# diffamp.net
KiCad netlist of a schematic drawn in Altium Designer
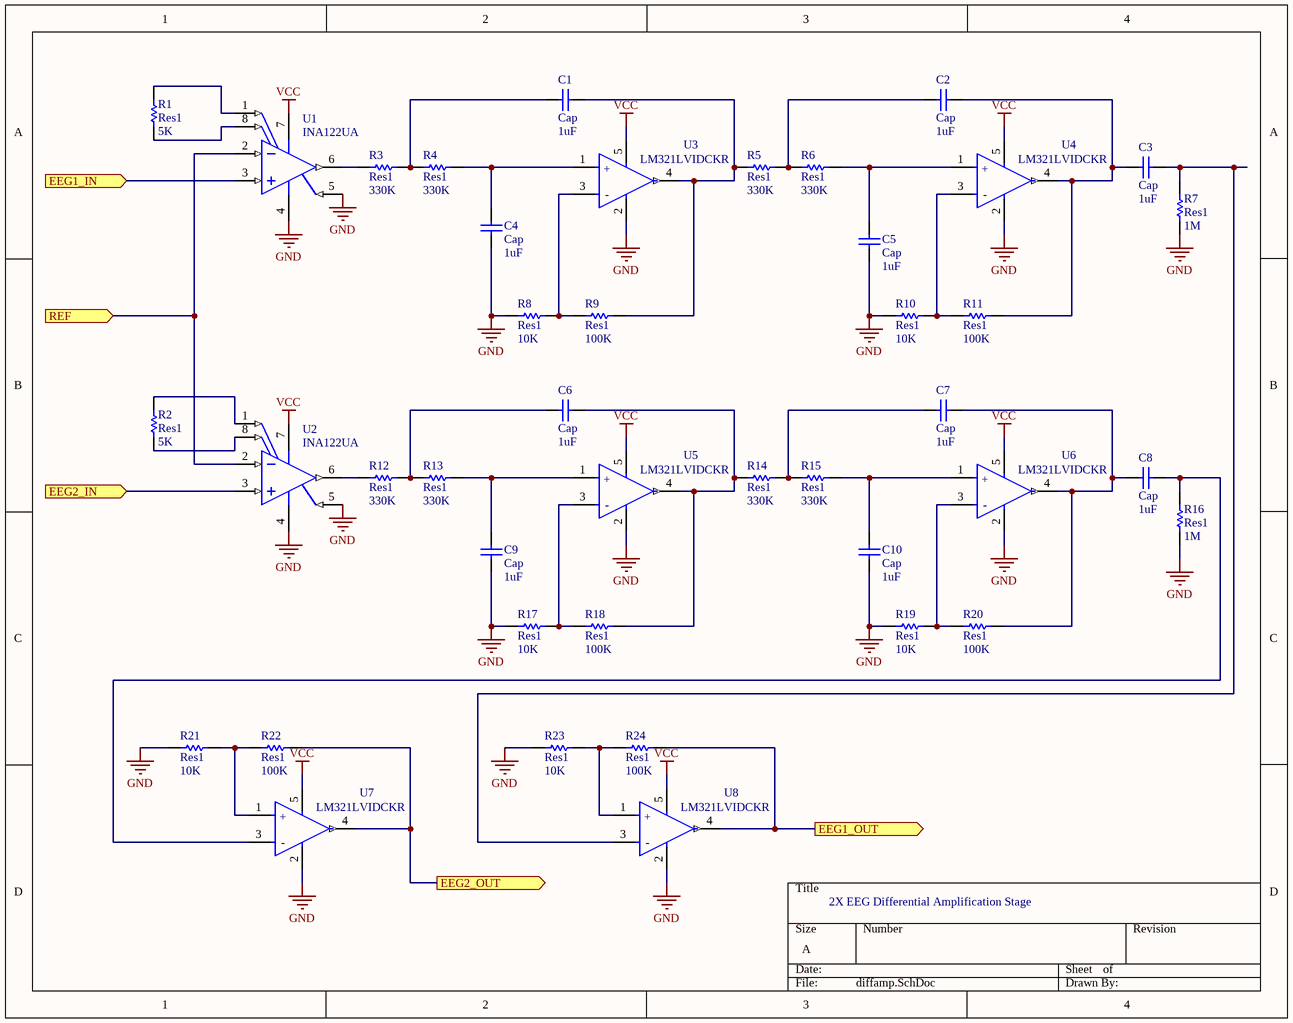
[diagram p0: diffamp.SchDoc]

(export (version "E")
  (design (tool "Eeschema 10.0.6"))
  (components
    (comp (ref "C1")
      (value "Cap")
      (footprint "6-0805_M")
      (description "Capacitor")
      (fields (field (name "ALTIUM_VALUE") "1uF") (field (name "PUBLISHER") "Altium Limited"))
      (libsource (lib "Miscellaneous Devices") (part "Cap"))
    )
    (comp (ref "C2")
      (value "Cap")
      (footprint "6-0805_M")
      (description "Capacitor")
      (fields (field (name "ALTIUM_VALUE") "1uF") (field (name "PUBLISHER") "Altium Limited"))
      (libsource (lib "Miscellaneous Devices") (part "Cap"))
    )
    (comp (ref "C3")
      (value "Cap")
      (footprint "6-0805_M")
      (description "Capacitor")
      (fields (field (name "ALTIUM_VALUE") "1uF") (field (name "PUBLISHER") "Altium Limited"))
      (libsource (lib "Miscellaneous Devices") (part "Cap"))
    )
    (comp (ref "C4")
      (value "Cap")
      (footprint "6-0805_M")
      (description "Capacitor")
      (fields (field (name "ALTIUM_VALUE") "1uF") (field (name "PUBLISHER") "Altium Limited"))
      (libsource (lib "Miscellaneous Devices") (part "Cap"))
    )
    (comp (ref "C5")
      (value "Cap")
      (footprint "6-0805_M")
      (description "Capacitor")
      (fields (field (name "ALTIUM_VALUE") "1uF") (field (name "PUBLISHER") "Altium Limited"))
      (libsource (lib "Miscellaneous Devices") (part "Cap"))
    )
    (comp (ref "C6")
      (value "Cap")
      (footprint "6-0805_M")
      (description "Capacitor")
      (fields (field (name "ALTIUM_VALUE") "1uF") (field (name "PUBLISHER") "Altium Limited"))
      (libsource (lib "Miscellaneous Devices") (part "Cap"))
    )
    (comp (ref "C7")
      (value "Cap")
      (footprint "6-0805_M")
      (description "Capacitor")
      (fields (field (name "ALTIUM_VALUE") "1uF") (field (name "PUBLISHER") "Altium Limited"))
      (libsource (lib "Miscellaneous Devices") (part "Cap"))
    )
    (comp (ref "C8")
      (value "Cap")
      (footprint "6-0805_M")
      (description "Capacitor")
      (fields (field (name "ALTIUM_VALUE") "1uF") (field (name "PUBLISHER") "Altium Limited"))
      (libsource (lib "Miscellaneous Devices") (part "Cap"))
    )
    (comp (ref "C9")
      (value "Cap")
      (footprint "6-0805_M")
      (description "Capacitor")
      (fields (field (name "ALTIUM_VALUE") "1uF") (field (name "PUBLISHER") "Altium Limited"))
      (libsource (lib "Miscellaneous Devices") (part "Cap"))
    )
    (comp (ref "C10")
      (value "Cap")
      (footprint "6-0805_M")
      (description "Capacitor")
      (fields (field (name "ALTIUM_VALUE") "1uF") (field (name "PUBLISHER") "Altium Limited"))
      (libsource (lib "Miscellaneous Devices") (part "Cap"))
    )
    (comp (ref "R1")
      (value "Res1")
      (footprint "6-0805_M")
      (description "Resistor")
      (fields (field (name "ALTIUM_VALUE") "5K") (field (name "PUBLISHER") "Altium Limited"))
      (libsource (lib "Miscellaneous Devices") (part "Res1"))
    )
    (comp (ref "R2")
      (value "Res1")
      (footprint "6-0805_M")
      (description "Resistor")
      (fields (field (name "ALTIUM_VALUE") "5K") (field (name "PUBLISHER") "Altium Limited"))
      (libsource (lib "Miscellaneous Devices") (part "Res1"))
    )
    (comp (ref "R3")
      (value "Res1")
      (footprint "6-0805_M")
      (description "Resistor")
      (fields (field (name "ALTIUM_VALUE") "330K") (field (name "PUBLISHER") "Altium Limited"))
      (libsource (lib "Miscellaneous Devices") (part "Res1"))
    )
    (comp (ref "R4")
      (value "Res1")
      (footprint "6-0805_M")
      (description "Resistor")
      (fields (field (name "ALTIUM_VALUE") "330K") (field (name "PUBLISHER") "Altium Limited"))
      (libsource (lib "Miscellaneous Devices") (part "Res1"))
    )
    (comp (ref "R5")
      (value "Res1")
      (footprint "6-0805_M")
      (description "Resistor")
      (fields (field (name "ALTIUM_VALUE") "330K") (field (name "PUBLISHER") "Altium Limited"))
      (libsource (lib "Miscellaneous Devices") (part "Res1"))
    )
    (comp (ref "R6")
      (value "Res1")
      (footprint "6-0805_M")
      (description "Resistor")
      (fields (field (name "ALTIUM_VALUE") "330K") (field (name "PUBLISHER") "Altium Limited"))
      (libsource (lib "Miscellaneous Devices") (part "Res1"))
    )
    (comp (ref "R7")
      (value "Res1")
      (footprint "6-0805_M")
      (description "Resistor")
      (fields (field (name "ALTIUM_VALUE") "1M") (field (name "PUBLISHER") "Altium Limited"))
      (libsource (lib "Miscellaneous Devices") (part "Res1"))
    )
    (comp (ref "R8")
      (value "Res1")
      (footprint "6-0805_M")
      (description "Resistor")
      (fields (field (name "ALTIUM_VALUE") "10K") (field (name "PUBLISHER") "Altium Limited"))
      (libsource (lib "Miscellaneous Devices") (part "Res1"))
    )
    (comp (ref "R9")
      (value "Res1")
      (footprint "6-0805_M")
      (description "Resistor")
      (fields (field (name "ALTIUM_VALUE") "100K") (field (name "PUBLISHER") "Altium Limited"))
      (libsource (lib "Miscellaneous Devices") (part "Res1"))
    )
    (comp (ref "R10")
      (value "Res1")
      (footprint "6-0805_M")
      (description "Resistor")
      (fields (field (name "ALTIUM_VALUE") "10K") (field (name "PUBLISHER") "Altium Limited"))
      (libsource (lib "Miscellaneous Devices") (part "Res1"))
    )
    (comp (ref "R11")
      (value "Res1")
      (footprint "6-0805_M")
      (description "Resistor")
      (fields (field (name "ALTIUM_VALUE") "100K") (field (name "PUBLISHER") "Altium Limited"))
      (libsource (lib "Miscellaneous Devices") (part "Res1"))
    )
    (comp (ref "R12")
      (value "Res1")
      (footprint "6-0805_M")
      (description "Resistor")
      (fields (field (name "ALTIUM_VALUE") "330K") (field (name "PUBLISHER") "Altium Limited"))
      (libsource (lib "Miscellaneous Devices") (part "Res1"))
    )
    (comp (ref "R13")
      (value "Res1")
      (footprint "6-0805_M")
      (description "Resistor")
      (fields (field (name "ALTIUM_VALUE") "330K") (field (name "PUBLISHER") "Altium Limited"))
      (libsource (lib "Miscellaneous Devices") (part "Res1"))
    )
    (comp (ref "R14")
      (value "Res1")
      (footprint "6-0805_M")
      (description "Resistor")
      (fields (field (name "ALTIUM_VALUE") "330K") (field (name "PUBLISHER") "Altium Limited"))
      (libsource (lib "Miscellaneous Devices") (part "Res1"))
    )
    (comp (ref "R15")
      (value "Res1")
      (footprint "6-0805_M")
      (description "Resistor")
      (fields (field (name "ALTIUM_VALUE") "330K") (field (name "PUBLISHER") "Altium Limited"))
      (libsource (lib "Miscellaneous Devices") (part "Res1"))
    )
    (comp (ref "R16")
      (value "Res1")
      (footprint "6-0805_M")
      (description "Resistor")
      (fields (field (name "ALTIUM_VALUE") "1M") (field (name "PUBLISHER") "Altium Limited"))
      (libsource (lib "Miscellaneous Devices") (part "Res1"))
    )
    (comp (ref "R17")
      (value "Res1")
      (footprint "6-0805_M")
      (description "Resistor")
      (fields (field (name "ALTIUM_VALUE") "10K") (field (name "PUBLISHER") "Altium Limited"))
      (libsource (lib "Miscellaneous Devices") (part "Res1"))
    )
    (comp (ref "R18")
      (value "Res1")
      (footprint "6-0805_M")
      (description "Resistor")
      (fields (field (name "ALTIUM_VALUE") "100K") (field (name "PUBLISHER") "Altium Limited"))
      (libsource (lib "Miscellaneous Devices") (part "Res1"))
    )
    (comp (ref "R19")
      (value "Res1")
      (footprint "6-0805_M")
      (description "Resistor")
      (fields (field (name "ALTIUM_VALUE") "10K") (field (name "PUBLISHER") "Altium Limited"))
      (libsource (lib "Miscellaneous Devices") (part "Res1"))
    )
    (comp (ref "R20")
      (value "Res1")
      (footprint "6-0805_M")
      (description "Resistor")
      (fields (field (name "ALTIUM_VALUE") "100K") (field (name "PUBLISHER") "Altium Limited"))
      (libsource (lib "Miscellaneous Devices") (part "Res1"))
    )
    (comp (ref "R21")
      (value "Res1")
      (footprint "6-0805_M")
      (description "Resistor")
      (fields (field (name "ALTIUM_VALUE") "10K") (field (name "PUBLISHER") "Altium Limited"))
      (libsource (lib "Miscellaneous Devices") (part "Res1"))
    )
    (comp (ref "R22")
      (value "Res1")
      (footprint "6-0805_M")
      (description "Resistor")
      (fields (field (name "ALTIUM_VALUE") "100K") (field (name "PUBLISHER") "Altium Limited"))
      (libsource (lib "Miscellaneous Devices") (part "Res1"))
    )
    (comp (ref "R23")
      (value "Res1")
      (footprint "6-0805_M")
      (description "Resistor")
      (fields (field (name "ALTIUM_VALUE") "10K") (field (name "PUBLISHER") "Altium Limited"))
      (libsource (lib "Miscellaneous Devices") (part "Res1"))
    )
    (comp (ref "R24")
      (value "Res1")
      (footprint "6-0805_M")
      (description "Resistor")
      (fields (field (name "ALTIUM_VALUE") "100K") (field (name "PUBLISHER") "Altium Limited"))
      (libsource (lib "Miscellaneous Devices") (part "Res1"))
    )
    (comp (ref "U1")
      (value "INA122UA")
      (footprint "D0008A_L")
      (fields (field (name "MANUFACTURER") "Texas Instruments"))
      (libsource (lib "Altium Content Vault") (part "TI-INA1XX-8"))
    )
    (comp (ref "U2")
      (value "INA122UA")
      (footprint "D0008A_L")
      (fields (field (name "MANUFACTURER") "Texas Instruments"))
      (libsource (lib "Altium Content Vault") (part "TI-INA1XX-8"))
    )
    (comp (ref "U3")
      (value "LM321LVIDCKR")
      (footprint "FP-DCK0005A-IPC_B")
      (description "IC OPAMP GP 1 CIRCUIT SC70-5")
      (libsource (lib "Altium Content Vault") (part "471d8b929410cd356ad4b122f572ce5"))
    )
    (comp (ref "U4")
      (value "LM321LVIDCKR")
      (footprint "FP-DCK0005A-IPC_B")
      (description "IC OPAMP GP 1 CIRCUIT SC70-5")
      (libsource (lib "Altium Content Vault") (part "471d8b929410cd356ad4b122f572ce5"))
    )
    (comp (ref "U5")
      (value "LM321LVIDCKR")
      (footprint "FP-DCK0005A-IPC_B")
      (description "IC OPAMP GP 1 CIRCUIT SC70-5")
      (libsource (lib "Altium Content Vault") (part "471d8b929410cd356ad4b122f572ce5"))
    )
    (comp (ref "U6")
      (value "LM321LVIDCKR")
      (footprint "FP-DCK0005A-IPC_B")
      (description "IC OPAMP GP 1 CIRCUIT SC70-5")
      (libsource (lib "Altium Content Vault") (part "471d8b929410cd356ad4b122f572ce5"))
    )
    (comp (ref "U7")
      (value "LM321LVIDCKR")
      (footprint "FP-DCK0005A-IPC_B")
      (description "IC OPAMP GP 1 CIRCUIT SC70-5")
      (libsource (lib "Altium Content Vault") (part "471d8b929410cd356ad4b122f572ce5"))
    )
    (comp (ref "U8")
      (value "LM321LVIDCKR")
      (footprint "FP-DCK0005A-IPC_B")
      (description "IC OPAMP GP 1 CIRCUIT SC70-5")
      (libsource (lib "Altium Content Vault") (part "471d8b929410cd356ad4b122f572ce5"))
    )
  )
  (nets
    (net (code "1") (name "/EEG1_IN") (class "Default")
      (node (ref "U1") (pin "3") (pinfunction "VIN+_3") (pintype "input"))
    )
    (net (code "2") (name "/EEG1_OUT") (class "Default")
      (node (ref "R24") (pin "2") (pinfunction "2_2") (pintype "passive"))
      (node (ref "U8") (pin "4") (pinfunction "OUT_4") (pintype "output"))
    )
    (net (code "3") (name "/EEG2_IN") (class "Default")
      (node (ref "U2") (pin "3") (pinfunction "VIN+_3") (pintype "input"))
    )
    (net (code "4") (name "/EEG2_OUT") (class "Default")
      (node (ref "R22") (pin "2") (pinfunction "2_2") (pintype "passive"))
      (node (ref "U7") (pin "4") (pinfunction "OUT_4") (pintype "output"))
    )
    (net (code "5") (name "/REF") (class "Default")
      (node (ref "U1") (pin "2") (pinfunction "VIN-_2") (pintype "input"))
      (node (ref "U2") (pin "2") (pinfunction "VIN-_2") (pintype "input"))
    )
    (net (code "6") (name "GND") (class "Default")
      (node (ref "C10") (pin "2") (pinfunction "2_2") (pintype "passive"))
      (node (ref "C4") (pin "2") (pinfunction "2_2") (pintype "passive"))
      (node (ref "C5") (pin "2") (pinfunction "2_2") (pintype "passive"))
      (node (ref "C9") (pin "2") (pinfunction "2_2") (pintype "passive"))
      (node (ref "R10") (pin "1") (pinfunction "1_1") (pintype "passive"))
      (node (ref "R16") (pin "2") (pinfunction "2_2") (pintype "passive"))
      (node (ref "R17") (pin "1") (pinfunction "1_1") (pintype "passive"))
      (node (ref "R19") (pin "1") (pinfunction "1_1") (pintype "passive"))
      (node (ref "R21") (pin "1") (pinfunction "1_1") (pintype "passive"))
      (node (ref "R23") (pin "1") (pinfunction "1_1") (pintype "passive"))
      (node (ref "R7") (pin "2") (pinfunction "2_2") (pintype "passive"))
      (node (ref "R8") (pin "1") (pinfunction "1_1") (pintype "passive"))
      (node (ref "U1") (pin "4") (pinfunction "V-_4") (pintype "power_in"))
      (node (ref "U1") (pin "5") (pinfunction "REF_5") (pintype "input"))
      (node (ref "U2") (pin "4") (pinfunction "V-_4") (pintype "power_in"))
      (node (ref "U2") (pin "5") (pinfunction "REF_5") (pintype "input"))
      (node (ref "U3") (pin "2") (pinfunction "V-_2") (pintype "power_in"))
      (node (ref "U4") (pin "2") (pinfunction "V-_2") (pintype "power_in"))
      (node (ref "U5") (pin "2") (pinfunction "V-_2") (pintype "power_in"))
      (node (ref "U6") (pin "2") (pinfunction "V-_2") (pintype "power_in"))
      (node (ref "U7") (pin "2") (pinfunction "V-_2") (pintype "power_in"))
      (node (ref "U8") (pin "2") (pinfunction "V-_2") (pintype "power_in"))
    )
    (net (code "7") (name "Net-(C1-Pad1)") (class "Default")
      (node (ref "C1") (pin "1") (pinfunction "1_1") (pintype "passive"))
      (node (ref "R3") (pin "2") (pinfunction "2_2") (pintype "passive"))
      (node (ref "R4") (pin "1") (pinfunction "1_1") (pintype "passive"))
    )
    (net (code "8") (name "Net-(C2-Pad1)") (class "Default")
      (node (ref "C2") (pin "1") (pinfunction "1_1") (pintype "passive"))
      (node (ref "R5") (pin "2") (pinfunction "2_2") (pintype "passive"))
      (node (ref "R6") (pin "1") (pinfunction "1_1") (pintype "passive"))
    )
    (net (code "9") (name "Net-(C6-Pad1)") (class "Default")
      (node (ref "C6") (pin "1") (pinfunction "1_1") (pintype "passive"))
      (node (ref "R12") (pin "2") (pinfunction "2_2") (pintype "passive"))
      (node (ref "R13") (pin "1") (pinfunction "1_1") (pintype "passive"))
    )
    (net (code "10") (name "Net-(C7-Pad1)") (class "Default")
      (node (ref "C7") (pin "1") (pinfunction "1_1") (pintype "passive"))
      (node (ref "R14") (pin "2") (pinfunction "2_2") (pintype "passive"))
      (node (ref "R15") (pin "1") (pinfunction "1_1") (pintype "passive"))
    )
    (net (code "11") (name "Net-(R1-Pad1)") (class "Default")
      (node (ref "R1") (pin "1") (pinfunction "1_1") (pintype "passive"))
      (node (ref "U1") (pin "1") (pinfunction "RG_1") (pintype "input"))
    )
    (net (code "12") (name "Net-(R1-Pad2)") (class "Default")
      (node (ref "R1") (pin "2") (pinfunction "2_2") (pintype "passive"))
      (node (ref "U1") (pin "8") (pinfunction "RG_8") (pintype "input"))
    )
    (net (code "13") (name "Net-(R2-Pad1)") (class "Default")
      (node (ref "R2") (pin "1") (pinfunction "1_1") (pintype "passive"))
      (node (ref "U2") (pin "1") (pinfunction "RG_1") (pintype "input"))
    )
    (net (code "14") (name "Net-(R2-Pad2)") (class "Default")
      (node (ref "R2") (pin "2") (pinfunction "2_2") (pintype "passive"))
      (node (ref "U2") (pin "8") (pinfunction "RG_8") (pintype "input"))
    )
    (net (code "15") (name "Net-(U1-VO)") (class "Default")
      (node (ref "R3") (pin "1") (pinfunction "1_1") (pintype "passive"))
      (node (ref "U1") (pin "6") (pinfunction "VO_6") (pintype "output"))
    )
    (net (code "16") (name "Net-(U2-VO)") (class "Default")
      (node (ref "R12") (pin "1") (pinfunction "1_1") (pintype "passive"))
      (node (ref "U2") (pin "6") (pinfunction "VO_6") (pintype "output"))
    )
    (net (code "17") (name "Net-(U3-IN+)") (class "Default")
      (node (ref "C4") (pin "1") (pinfunction "1_1") (pintype "passive"))
      (node (ref "R4") (pin "2") (pinfunction "2_2") (pintype "passive"))
      (node (ref "U3") (pin "1") (pinfunction "IN+_1") (pintype "tri_state"))
    )
    (net (code "18") (name "Net-(U3-IN-)") (class "Default")
      (node (ref "R8") (pin "2") (pinfunction "2_2") (pintype "passive"))
      (node (ref "R9") (pin "1") (pinfunction "1_1") (pintype "passive"))
      (node (ref "U3") (pin "3") (pinfunction "IN-_3") (pintype "tri_state"))
    )
    (net (code "19") (name "Net-(U3-OUT)") (class "Default")
      (node (ref "C1") (pin "2") (pinfunction "2_2") (pintype "passive"))
      (node (ref "R5") (pin "1") (pinfunction "1_1") (pintype "passive"))
      (node (ref "R9") (pin "2") (pinfunction "2_2") (pintype "passive"))
      (node (ref "U3") (pin "4") (pinfunction "OUT_4") (pintype "output"))
    )
    (net (code "20") (name "Net-(U4-IN+)") (class "Default")
      (node (ref "C5") (pin "1") (pinfunction "1_1") (pintype "passive"))
      (node (ref "R6") (pin "2") (pinfunction "2_2") (pintype "passive"))
      (node (ref "U4") (pin "1") (pinfunction "IN+_1") (pintype "tri_state"))
    )
    (net (code "21") (name "Net-(U4-IN-)") (class "Default")
      (node (ref "R10") (pin "2") (pinfunction "2_2") (pintype "passive"))
      (node (ref "R11") (pin "1") (pinfunction "1_1") (pintype "passive"))
      (node (ref "U4") (pin "3") (pinfunction "IN-_3") (pintype "tri_state"))
    )
    (net (code "22") (name "Net-(U4-OUT)") (class "Default")
      (node (ref "C2") (pin "2") (pinfunction "2_2") (pintype "passive"))
      (node (ref "C3") (pin "1") (pinfunction "1_1") (pintype "passive"))
      (node (ref "R11") (pin "2") (pinfunction "2_2") (pintype "passive"))
      (node (ref "U4") (pin "4") (pinfunction "OUT_4") (pintype "output"))
    )
    (net (code "23") (name "Net-(U5-IN+)") (class "Default")
      (node (ref "C9") (pin "1") (pinfunction "1_1") (pintype "passive"))
      (node (ref "R13") (pin "2") (pinfunction "2_2") (pintype "passive"))
      (node (ref "U5") (pin "1") (pinfunction "IN+_1") (pintype "tri_state"))
    )
    (net (code "24") (name "Net-(U5-IN-)") (class "Default")
      (node (ref "R17") (pin "2") (pinfunction "2_2") (pintype "passive"))
      (node (ref "R18") (pin "1") (pinfunction "1_1") (pintype "passive"))
      (node (ref "U5") (pin "3") (pinfunction "IN-_3") (pintype "tri_state"))
    )
    (net (code "25") (name "Net-(U5-OUT)") (class "Default")
      (node (ref "C6") (pin "2") (pinfunction "2_2") (pintype "passive"))
      (node (ref "R14") (pin "1") (pinfunction "1_1") (pintype "passive"))
      (node (ref "R18") (pin "2") (pinfunction "2_2") (pintype "passive"))
      (node (ref "U5") (pin "4") (pinfunction "OUT_4") (pintype "output"))
    )
    (net (code "26") (name "Net-(U6-IN+)") (class "Default")
      (node (ref "C10") (pin "1") (pinfunction "1_1") (pintype "passive"))
      (node (ref "R15") (pin "2") (pinfunction "2_2") (pintype "passive"))
      (node (ref "U6") (pin "1") (pinfunction "IN+_1") (pintype "tri_state"))
    )
    (net (code "27") (name "Net-(U6-IN-)") (class "Default")
      (node (ref "R19") (pin "2") (pinfunction "2_2") (pintype "passive"))
      (node (ref "R20") (pin "1") (pinfunction "1_1") (pintype "passive"))
      (node (ref "U6") (pin "3") (pinfunction "IN-_3") (pintype "tri_state"))
    )
    (net (code "28") (name "Net-(U6-OUT)") (class "Default")
      (node (ref "C7") (pin "2") (pinfunction "2_2") (pintype "passive"))
      (node (ref "C8") (pin "1") (pinfunction "1_1") (pintype "passive"))
      (node (ref "R20") (pin "2") (pinfunction "2_2") (pintype "passive"))
      (node (ref "U6") (pin "4") (pinfunction "OUT_4") (pintype "output"))
    )
    (net (code "29") (name "Net-(U7-IN+)") (class "Default")
      (node (ref "R21") (pin "2") (pinfunction "2_2") (pintype "passive"))
      (node (ref "R22") (pin "1") (pinfunction "1_1") (pintype "passive"))
      (node (ref "U7") (pin "1") (pinfunction "IN+_1") (pintype "tri_state"))
    )
    (net (code "30") (name "Net-(U7-IN-)") (class "Default")
      (node (ref "C8") (pin "2") (pinfunction "2_2") (pintype "passive"))
      (node (ref "R16") (pin "1") (pinfunction "1_1") (pintype "passive"))
      (node (ref "U7") (pin "3") (pinfunction "IN-_3") (pintype "tri_state"))
    )
    (net (code "31") (name "Net-(U8-IN+)") (class "Default")
      (node (ref "R23") (pin "2") (pinfunction "2_2") (pintype "passive"))
      (node (ref "R24") (pin "1") (pinfunction "1_1") (pintype "passive"))
      (node (ref "U8") (pin "1") (pinfunction "IN+_1") (pintype "tri_state"))
    )
    (net (code "32") (name "Net-(U8-IN-)") (class "Default")
      (node (ref "C3") (pin "2") (pinfunction "2_2") (pintype "passive"))
      (node (ref "R7") (pin "1") (pinfunction "1_1") (pintype "passive"))
      (node (ref "U8") (pin "3") (pinfunction "IN-_3") (pintype "tri_state"))
    )
    (net (code "33") (name "VCC") (class "Default")
      (node (ref "U1") (pin "7") (pinfunction "V+_7") (pintype "power_in"))
      (node (ref "U2") (pin "7") (pinfunction "V+_7") (pintype "power_in"))
      (node (ref "U3") (pin "5") (pinfunction "V+_5") (pintype "power_in"))
      (node (ref "U4") (pin "5") (pinfunction "V+_5") (pintype "power_in"))
      (node (ref "U5") (pin "5") (pinfunction "V+_5") (pintype "power_in"))
      (node (ref "U6") (pin "5") (pinfunction "V+_5") (pintype "power_in"))
      (node (ref "U7") (pin "5") (pinfunction "V+_5") (pintype "power_in"))
      (node (ref "U8") (pin "5") (pinfunction "V+_5") (pintype "power_in"))
    )
  )
)
